# Main.net
KiCad netlist of a schematic drawn in Altium Designer
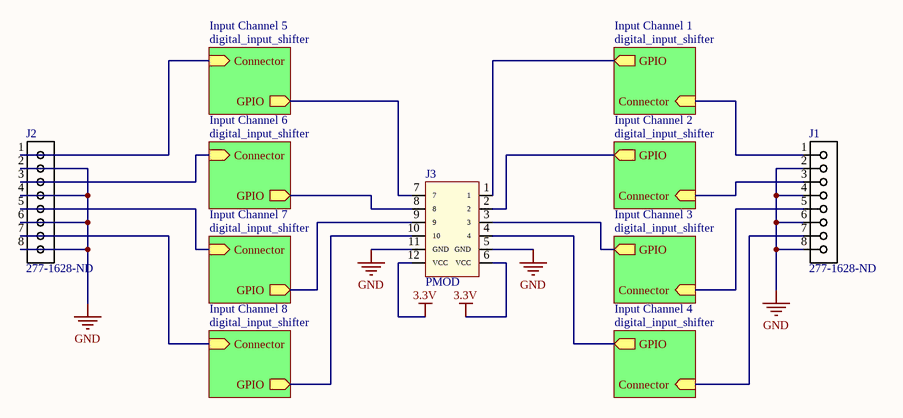
[diagram p0: Main.SchDoc]

(export (version "E")
  (design (tool "Eeschema 10.0.6"))
  (components
    (comp (ref "J1")
      (value "Phoenix Teminal Block")
      (footprint "8pin_phoenix_terminal_block:PHOENIX_8")
      (fields (field (name "SUPPLIER PART NUMBER 1") "277-1628-ND"))
      (libsource (lib "8pin_phoenix_terminal_block") (part "Phoenix Teminal Block"))
    )
    (comp (ref "J2")
      (value "Phoenix Teminal Block")
      (footprint "8pin_phoenix_terminal_block:PHOENIX_8")
      (fields (field (name "SUPPLIER PART NUMBER 1") "277-1628-ND"))
      (libsource (lib "8pin_phoenix_terminal_block") (part "Phoenix Teminal Block"))
    )
    (comp (ref "J3")
      (value "PMOD")
      (footprint "pmod_male_6x2 footprint:PMOD_6x2_male")
      (description "2x6 PMOD right angle board connector.")
      (libsource (lib "pmod_male_2x6") (part "PMOD Male 2-row"))
    )
  )
  (nets
    (net (code "1") (name "/Connector") (class "Default")
      (node (ref "J1") (pin "7") (pinfunction "7_7") (pintype "passive"))
    )
    (net (code "2") (name "/Connector_1") (class "Default")
      (node (ref "J2") (pin "5") (pinfunction "5_5") (pintype "passive"))
    )
    (net (code "3") (name "/Connector_2") (class "Default")
      (node (ref "J2") (pin "3") (pinfunction "3_3") (pintype "passive"))
    )
    (net (code "4") (name "/Connector_3") (class "Default")
      (node (ref "J2") (pin "7") (pinfunction "7_7") (pintype "passive"))
    )
    (net (code "5") (name "/Connector_4") (class "Default")
      (node (ref "J2") (pin "1") (pinfunction "1_1") (pintype "passive"))
    )
    (net (code "6") (name "/Connector_5") (class "Default")
      (node (ref "J1") (pin "1") (pinfunction "1_1") (pintype "passive"))
    )
    (net (code "7") (name "/Connector_6") (class "Default")
      (node (ref "J1") (pin "3") (pinfunction "3_3") (pintype "passive"))
    )
    (net (code "8") (name "/Connector_7") (class "Default")
      (node (ref "J1") (pin "5") (pinfunction "5_5") (pintype "passive"))
    )
    (net (code "9") (name "/GPIO") (class "Default")
      (node (ref "J3") (pin "4") (pinfunction "4_4") (pintype "passive"))
    )
    (net (code "10") (name "/GPIO_1") (class "Default")
      (node (ref "J3") (pin "8") (pinfunction "8_8") (pintype "passive"))
    )
    (net (code "11") (name "/GPIO_2") (class "Default")
      (node (ref "J3") (pin "9") (pinfunction "9_9") (pintype "passive"))
    )
    (net (code "12") (name "/GPIO_3") (class "Default")
      (node (ref "J3") (pin "10") (pinfunction "10_10") (pintype "passive"))
    )
    (net (code "13") (name "/GPIO_4") (class "Default")
      (node (ref "J3") (pin "7") (pinfunction "7_7") (pintype "passive"))
    )
    (net (code "14") (name "/GPIO_5") (class "Default")
      (node (ref "J3") (pin "1") (pinfunction "1_1") (pintype "passive"))
    )
    (net (code "15") (name "/GPIO_6") (class "Default")
      (node (ref "J3") (pin "2") (pinfunction "2_2") (pintype "passive"))
    )
    (net (code "16") (name "/GPIO_7") (class "Default")
      (node (ref "J3") (pin "3") (pinfunction "3_3") (pintype "passive"))
    )
    (net (code "17") (name "3.3V") (class "Default")
      (node (ref "J3") (pin "12") (pinfunction "VCC_12") (pintype "passive"))
      (node (ref "J3") (pin "6") (pinfunction "VCC_6") (pintype "passive"))
    )
    (net (code "18") (name "GND") (class "Default")
      (node (ref "J1") (pin "2") (pinfunction "2_2") (pintype "passive"))
      (node (ref "J1") (pin "4") (pinfunction "4_4") (pintype "passive"))
      (node (ref "J1") (pin "6") (pinfunction "6_6") (pintype "passive"))
      (node (ref "J1") (pin "8") (pinfunction "8_8") (pintype "passive"))
      (node (ref "J2") (pin "2") (pinfunction "2_2") (pintype "passive"))
      (node (ref "J2") (pin "4") (pinfunction "4_4") (pintype "passive"))
      (node (ref "J2") (pin "6") (pinfunction "6_6") (pintype "passive"))
      (node (ref "J2") (pin "8") (pinfunction "8_8") (pintype "passive"))
      (node (ref "J3") (pin "11") (pinfunction "GND_11") (pintype "passive"))
      (node (ref "J3") (pin "5") (pinfunction "GND_5") (pintype "passive"))
    )
  )
)
